# rc4_1_1.net
KiCad netlist of a schematic drawn in EAGLE
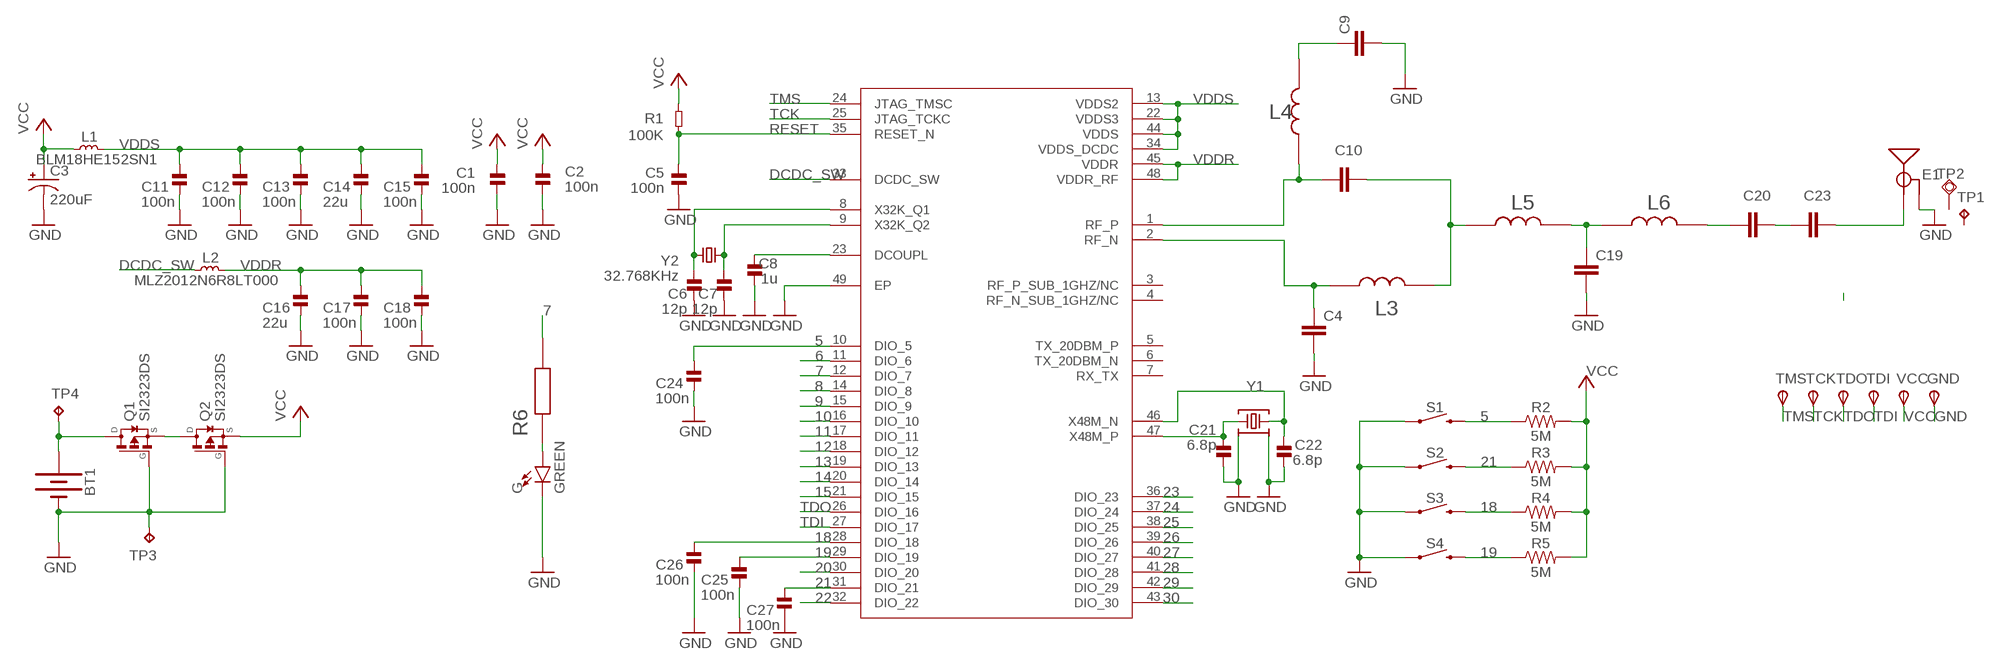
[diagram p0: schematic, sheet 1]

(export (version "E")
  (design (tool "Eeschema 10.0.6"))
  (components
    (comp (ref "BT1")
      (value "BATTERY-20MM_SMD_4LEGS_OVERPASTE")
      (footprint "eagle-import:BATTCON_20MM_4LEGS_OVERPASTE")
      (libsource (lib "eagle-import") (part "BATTERY-20MM_SMD_4LEGS_OVERPASTE"))
    )
    (comp (ref "C1")
      (value "100n")
      (footprint "eagle-import:_PKG_C_0402")
      (libsource (lib "eagle-import") (part "CAP-0402"))
    )
    (comp (ref "C2")
      (value "100n")
      (footprint "eagle-import:_PKG_C_0402")
      (libsource (lib "eagle-import") (part "CAP-0402"))
    )
    (comp (ref "C3")
      (value "220uF")
      (footprint "eagle-import:EIA3528")
      (libsource (lib "eagle-import") (part "47UF-POLAR-EIA3528-10V-10%"))
    )
    (comp (ref "C4")
      (value "1pf")
      (footprint "eagle-import:CAPC1005X40N")
      (fields (field (name "MF") "Yageo") (field (name "MP") "RC0402FR-073M6L"))
      (libsource (lib "eagle-import") (part "CAP0402"))
    )
    (comp (ref "C5")
      (value "100n")
      (footprint "eagle-import:_PKG_C_0402")
      (libsource (lib "eagle-import") (part "CAP-0402"))
    )
    (comp (ref "C6")
      (value "12p")
      (footprint "eagle-import:_PKG_C_0402")
      (libsource (lib "eagle-import") (part "CAP-0402"))
    )
    (comp (ref "C7")
      (value "12p")
      (footprint "eagle-import:_PKG_C_0402")
      (libsource (lib "eagle-import") (part "CAP-0402"))
    )
    (comp (ref "C8")
      (value "1u")
      (footprint "eagle-import:_PKG_C_0402")
      (libsource (lib "eagle-import") (part "CAP-0402"))
    )
    (comp (ref "C9")
      (value "12pF")
      (footprint "eagle-import:CAPC1005X40N")
      (fields (field (name "MF") "Yageo") (field (name "MP") "RC0402FR-073M6L"))
      (libsource (lib "eagle-import") (part "CAP0402"))
    )
    (comp (ref "C10")
      (value "1pF")
      (footprint "eagle-import:CAPC1005X40N")
      (fields (field (name "MF") "Yageo") (field (name "MP") "RC0402FR-073M6L"))
      (libsource (lib "eagle-import") (part "CAP0402"))
    )
    (comp (ref "C11")
      (value "100n")
      (footprint "eagle-import:_PKG_C_0402")
      (libsource (lib "eagle-import") (part "CAP-0402"))
    )
    (comp (ref "C12")
      (value "100n")
      (footprint "eagle-import:_PKG_C_0402")
      (libsource (lib "eagle-import") (part "CAP-0402"))
    )
    (comp (ref "C13")
      (value "100n")
      (footprint "eagle-import:_PKG_C_0402")
      (libsource (lib "eagle-import") (part "CAP-0402"))
    )
    (comp (ref "C14")
      (value "22u")
      (footprint "eagle-import:_PKG_C_0805")
      (libsource (lib "eagle-import") (part "CAP-0805"))
    )
    (comp (ref "C15")
      (value "100n")
      (footprint "eagle-import:_PKG_C_0402")
      (libsource (lib "eagle-import") (part "CAP-0402"))
    )
    (comp (ref "C16")
      (value "22u")
      (footprint "eagle-import:_PKG_C_0805")
      (libsource (lib "eagle-import") (part "CAP-0805"))
    )
    (comp (ref "C17")
      (value "100n")
      (footprint "eagle-import:_PKG_C_0402")
      (libsource (lib "eagle-import") (part "CAP-0402"))
    )
    (comp (ref "C18")
      (value "100n")
      (footprint "eagle-import:_PKG_C_0402")
      (libsource (lib "eagle-import") (part "CAP-0402"))
    )
    (comp (ref "C19")
      (value "1pF")
      (footprint "eagle-import:CAPC1005X40N")
      (fields (field (name "MF") "Yageo") (field (name "MP") "RC0402FR-073M6L"))
      (libsource (lib "eagle-import") (part "CAP0402"))
    )
    (comp (ref "C20")
      (value "12p")
      (footprint "eagle-import:CAPC1005X40N")
      (fields (field (name "MF") "Yageo") (field (name "MP") "RC0402FR-073M6L"))
      (libsource (lib "eagle-import") (part "CAP0402"))
    )
    (comp (ref "C21")
      (value "6.8p")
      (footprint "eagle-import:_PKG_C_0402")
      (libsource (lib "eagle-import") (part "CAP-0402"))
    )
    (comp (ref "C22")
      (value "6.8p")
      (footprint "eagle-import:_PKG_C_0402")
      (libsource (lib "eagle-import") (part "CAP-0402"))
    )
    (comp (ref "C23")
      (value "1.8pF")
      (footprint "eagle-import:CAPC1005X40N")
      (fields (field (name "MF") "Yageo") (field (name "MP") "RC0402FR-073M6L"))
      (libsource (lib "eagle-import") (part "CAP0402"))
    )
    (comp (ref "C24")
      (value "100n")
      (footprint "eagle-import:_PKG_C_0402")
      (libsource (lib "eagle-import") (part "CAP-0402"))
    )
    (comp (ref "C25")
      (value "100n")
      (footprint "eagle-import:_PKG_C_0402")
      (libsource (lib "eagle-import") (part "CAP-0402"))
    )
    (comp (ref "C26")
      (value "100n")
      (footprint "eagle-import:_PKG_C_0402")
      (libsource (lib "eagle-import") (part "CAP-0402"))
    )
    (comp (ref "C27")
      (value "100n")
      (footprint "eagle-import:_PKG_C_0402")
      (libsource (lib "eagle-import") (part "CAP-0402"))
    )
    (comp (ref "E1")
      (value "ANTENNA-GROUNDEDTRACE-15.2MM")
      (footprint "eagle-import:TRACE_ANTENNA_2.4GHZ_15.2MM")
      (libsource (lib "eagle-import") (part "ANTENNA-GROUNDEDTRACE-15.2MM"))
    )
    (comp (ref "G")
      (value "GREEN")
      (footprint "eagle-import:LED-0603")
      (libsource (lib "eagle-import") (part "LED-GREEN0603"))
    )
    (comp (ref "GND")
      (value "TPSTP11R")
      (footprint "eagle-import:TP11R")
      (libsource (lib "eagle-import") (part "TPSTP11R"))
    )
    (comp (ref "IC3")
      (value "CC2652R1FRGZ")
      (footprint "eagle-import:RGZ0048A-IPC_B")
      (fields
        (field (name "MANUFACTURER_PART_NUMBER") "CC2652P1FRGZR")
        (field (name "COPYRIGHT") "Copyright (C) 2022 Ultra Librarian. All rights reserved.")
      )
      (libsource (lib "eagle-import") (part "CC2652P1FRGZRRGZ0048A-IPC_B"))
    )
    (comp (ref "L1")
      (value "BLM18HE152SN1")
      (footprint "eagle-import:_PKG_L_0603")
      (libsource (lib "eagle-import") (part "INDUCTOR-0603"))
    )
    (comp (ref "L2")
      (value "MLZ2012N6R8LT000")
      (footprint "eagle-import:_PKG_C_0805")
      (libsource (lib "eagle-import") (part "INDUCTOR-0805"))
    )
    (comp (ref "L3")
      (value "2.4nH")
      (footprint "eagle-import:INDC1005X40N")
      (fields (field (name "MF") "Yageo") (field (name "MP") "RC0402FR-073M6L"))
      (libsource (lib "eagle-import") (part "IND0402IND0402"))
    )
    (comp (ref "L4")
      (value "2.4nH")
      (footprint "eagle-import:INDC1005X40N")
      (fields (field (name "MF") "Yageo") (field (name "MP") "RC0402FR-073M6L"))
      (libsource (lib "eagle-import") (part "IND0402IND0402"))
    )
    (comp (ref "L5")
      (value "2nH")
      (footprint "eagle-import:INDC1005X40N")
      (fields (field (name "MF") "Yageo") (field (name "MP") "RC0402FR-073M6L"))
      (libsource (lib "eagle-import") (part "IND0402IND0402"))
    )
    (comp (ref "L6")
      (value "2nH")
      (footprint "eagle-import:INDC1005X40N")
      (fields (field (name "MF") "Yageo") (field (name "MP") "RC0402FR-073M6L"))
      (libsource (lib "eagle-import") (part "IND0402IND0402"))
    )
    (comp (ref "Q1")
      (value "SI2323DS")
      (footprint "eagle-import:SOT23")
      (fields (field (name "MF") "Vishay Siliconix"))
      (libsource (lib "eagle-import") (part "SI2323DS"))
    )
    (comp (ref "Q2")
      (value "SI2323DS")
      (footprint "eagle-import:SOT23")
      (fields (field (name "MF") "Vishay Siliconix"))
      (libsource (lib "eagle-import") (part "SI2323DS"))
    )
    (comp (ref "R1")
      (value "100K")
      (footprint "eagle-import:_PKG_C_0402")
      (libsource (lib "eagle-import") (part "RES-0402"))
    )
    (comp (ref "R2")
      (value "5M")
      (footprint "eagle-import:0603")
      (libsource (lib "eagle-import") (part "2.49KOHM-0603-1/10W-1%"))
    )
    (comp (ref "R3")
      (value "5M")
      (footprint "eagle-import:0603")
      (libsource (lib "eagle-import") (part "2.49KOHM-0603-1/10W-1%"))
    )
    (comp (ref "R4")
      (value "5M")
      (footprint "eagle-import:0603")
      (libsource (lib "eagle-import") (part "2.49KOHM-0603-1/10W-1%"))
    )
    (comp (ref "R5")
      (value "5M")
      (footprint "eagle-import:0603")
      (libsource (lib "eagle-import") (part "2.49KOHM-0603-1/10W-1%"))
    )
    (comp (ref "R6")
      (value "2.2k")
      (footprint "eagle-import:RESC1005X40N")
      (fields (field (name "MF") "Yageo") (field (name "MP") "RC0402FR-073M6L"))
      (libsource (lib "eagle-import") (part "RES0402"))
    )
    (comp (ref "S1")
      (value "MOMENTARY-SWITCH-SPST-SMD-5.2MM")
      (footprint "eagle-import:TACTILE_SWITCH_SMD_5.2MM")
      (libsource (lib "eagle-import") (part "MOMENTARY-SWITCH-SPST-SMD-5.2MM"))
    )
    (comp (ref "S2")
      (value "MOMENTARY-SWITCH-SPST-SMD-5.2MM")
      (footprint "eagle-import:TACTILE_SWITCH_SMD_5.2MM")
      (libsource (lib "eagle-import") (part "MOMENTARY-SWITCH-SPST-SMD-5.2MM"))
    )
    (comp (ref "S3")
      (value "MOMENTARY-SWITCH-SPST-SMD-5.2MM")
      (footprint "eagle-import:TACTILE_SWITCH_SMD_5.2MM")
      (libsource (lib "eagle-import") (part "MOMENTARY-SWITCH-SPST-SMD-5.2MM"))
    )
    (comp (ref "S4")
      (value "MOMENTARY-SWITCH-SPST-SMD-5.2MM")
      (footprint "eagle-import:TACTILE_SWITCH_SMD_5.2MM")
      (libsource (lib "eagle-import") (part "MOMENTARY-SWITCH-SPST-SMD-5.2MM"))
    )
    (comp (ref "TCK")
      (value "TPSTP11R")
      (footprint "eagle-import:TP11R")
      (libsource (lib "eagle-import") (part "TPSTP11R"))
    )
    (comp (ref "TDI")
      (value "TPSTP11R")
      (footprint "eagle-import:TP11R")
      (libsource (lib "eagle-import") (part "TPSTP11R"))
    )
    (comp (ref "TDO")
      (value "TPSTP11R")
      (footprint "eagle-import:TP11R")
      (libsource (lib "eagle-import") (part "TPSTP11R"))
    )
    (comp (ref "TMS")
      (value "TPSTP11R")
      (footprint "eagle-import:TP11R")
      (libsource (lib "eagle-import") (part "TPSTP11R"))
    )
    (comp (ref "TP1")
      (value "TPTP06SQ")
      (footprint "eagle-import:TP05SQ")
      (libsource (lib "eagle-import") (part "TPTP06SQ"))
    )
    (comp (ref "TP2")
      (value "TPSQTP15SQ")
      (footprint "eagle-import:TP15SQ")
      (libsource (lib "eagle-import") (part "TPSQTP15SQ"))
    )
    (comp (ref "TP3")
      (value "TPB2,54")
      (footprint "eagle-import:B2,54")
      (libsource (lib "eagle-import") (part "testpad_385_TPB2,54"))
    )
    (comp (ref "TP4")
      (value "TPB2,54")
      (footprint "eagle-import:B2,54")
      (libsource (lib "eagle-import") (part "testpad_385_TPB2,54"))
    )
    (comp (ref "VCC")
      (value "TPSTP11R")
      (footprint "eagle-import:TP11R")
      (libsource (lib "eagle-import") (part "TPSTP11R"))
    )
    (comp (ref "Y1")
      (value "Q22FA12800150")
      (footprint "eagle-import:XTAL-4P-2016")
      (fields (field (name "DIGIKEY_PART") "1253-2042-1-ND") (field (name "MFG_PART") "CX2016DB48000C0FPLC1"))
      (libsource (lib "eagle-import") (part "48.000MHZ_CX2016DB48000C0FPLC1"))
    )
    (comp (ref "Y2")
      (value "32.768KHz")
      (footprint "eagle-import:XTAL-2P-3215")
      (fields (field (name "LCSC_PART") "C32346") (field (name "MFG_PART") "Q13FC1350000400"))
      (libsource (lib "eagle-import") (part "32.768KHZ_Q13FC1350000400"))
    )
  )
  (nets
    (net (code "1") (name "/5") (class "Default")
      (node (ref "C24") (pin "1") (pinfunction "1_1") (pintype "passive"))
      (node (ref "IC3") (pin "10") (pinfunction "DIO_5_10") (pintype "bidirectional"))
      (node (ref "R2") (pin "1") (pinfunction "1_1") (pintype "passive"))
      (node (ref "S1") (pin "3") (pinfunction "2_3") (pintype "passive"))
    )
    (net (code "2") (name "/6") (class "Default")
      (node (ref "IC3") (pin "11") (pinfunction "DIO_6_11") (pintype "bidirectional"))
    )
    (net (code "3") (name "/7") (class "Default")
      (node (ref "IC3") (pin "12") (pinfunction "DIO_7_12") (pintype "bidirectional"))
      (node (ref "R6") (pin "2") (pinfunction "2_2") (pintype "passive"))
    )
    (net (code "4") (name "/8") (class "Default")
      (node (ref "IC3") (pin "14") (pinfunction "DIO_8_14") (pintype "bidirectional"))
    )
    (net (code "5") (name "/9") (class "Default")
      (node (ref "IC3") (pin "15") (pinfunction "DIO_9_15") (pintype "bidirectional"))
    )
    (net (code "6") (name "/10") (class "Default")
      (node (ref "IC3") (pin "16") (pinfunction "DIO_10_16") (pintype "bidirectional"))
    )
    (net (code "7") (name "/11") (class "Default")
      (node (ref "IC3") (pin "17") (pinfunction "DIO_11_17") (pintype "bidirectional"))
    )
    (net (code "8") (name "/12") (class "Default")
      (node (ref "IC3") (pin "18") (pinfunction "DIO_12_18") (pintype "bidirectional"))
    )
    (net (code "9") (name "/13") (class "Default")
      (node (ref "IC3") (pin "19") (pinfunction "DIO_13_19") (pintype "bidirectional"))
    )
    (net (code "10") (name "/14") (class "Default")
      (node (ref "IC3") (pin "20") (pinfunction "DIO_14_20") (pintype "bidirectional"))
    )
    (net (code "11") (name "/15") (class "Default")
      (node (ref "IC3") (pin "21") (pinfunction "DIO_15_21") (pintype "bidirectional"))
    )
    (net (code "12") (name "/18") (class "Default")
      (node (ref "C26") (pin "1") (pinfunction "1_1") (pintype "passive"))
      (node (ref "IC3") (pin "28") (pinfunction "DIO_18_28") (pintype "bidirectional"))
      (node (ref "R4") (pin "1") (pinfunction "1_1") (pintype "passive"))
      (node (ref "S3") (pin "3") (pinfunction "2_3") (pintype "passive"))
    )
    (net (code "13") (name "/19") (class "Default")
      (node (ref "C25") (pin "1") (pinfunction "1_1") (pintype "passive"))
      (node (ref "IC3") (pin "29") (pinfunction "DIO_19_29") (pintype "bidirectional"))
      (node (ref "R5") (pin "1") (pinfunction "1_1") (pintype "passive"))
      (node (ref "S4") (pin "3") (pinfunction "2_3") (pintype "passive"))
    )
    (net (code "14") (name "/20") (class "Default")
      (node (ref "IC3") (pin "30") (pinfunction "DIO_20_30") (pintype "bidirectional"))
    )
    (net (code "15") (name "/21") (class "Default")
      (node (ref "C27") (pin "1") (pinfunction "1_1") (pintype "passive"))
      (node (ref "IC3") (pin "31") (pinfunction "DIO_21_31") (pintype "bidirectional"))
      (node (ref "R3") (pin "1") (pinfunction "1_1") (pintype "passive"))
      (node (ref "S2") (pin "3") (pinfunction "2_3") (pintype "passive"))
    )
    (net (code "16") (name "/22") (class "Default")
      (node (ref "IC3") (pin "32") (pinfunction "DIO_22_32") (pintype "bidirectional"))
    )
    (net (code "17") (name "/23") (class "Default")
      (node (ref "IC3") (pin "36") (pinfunction "DIO_23_36") (pintype "bidirectional"))
    )
    (net (code "18") (name "/24") (class "Default")
      (node (ref "IC3") (pin "37") (pinfunction "DIO_24_37") (pintype "bidirectional"))
    )
    (net (code "19") (name "/25") (class "Default")
      (node (ref "IC3") (pin "38") (pinfunction "DIO_25_38") (pintype "bidirectional"))
    )
    (net (code "20") (name "/26") (class "Default")
      (node (ref "IC3") (pin "39") (pinfunction "DIO_26_39") (pintype "bidirectional"))
    )
    (net (code "21") (name "/27") (class "Default")
      (node (ref "IC3") (pin "40") (pinfunction "DIO_27_40") (pintype "bidirectional"))
    )
    (net (code "22") (name "/28") (class "Default")
      (node (ref "IC3") (pin "41") (pinfunction "DIO_28_41") (pintype "bidirectional"))
    )
    (net (code "23") (name "/29") (class "Default")
      (node (ref "IC3") (pin "42") (pinfunction "DIO_29_42") (pintype "bidirectional"))
    )
    (net (code "24") (name "/30") (class "Default")
      (node (ref "IC3") (pin "43") (pinfunction "DIO_30_43") (pintype "bidirectional"))
    )
    (net (code "25") (name "/DCDC_SW") (class "Default")
      (node (ref "IC3") (pin "33") (pinfunction "DCDC_SW_33") (pintype "power_in"))
      (node (ref "L2") (pin "1") (pinfunction "1_1") (pintype "passive"))
    )
    (net (code "26") (name "/RESET") (class "Default")
      (node (ref "C5") (pin "2") (pinfunction "2_2") (pintype "passive"))
      (node (ref "IC3") (pin "35") (pinfunction "RESET_N_35") (pintype "input"))
      (node (ref "R1") (pin "1") (pinfunction "1_1") (pintype "passive"))
    )
    (net (code "27") (name "/TCK") (class "Default")
      (node (ref "IC3") (pin "25") (pinfunction "JTAG_TCKC_25") (pintype "input"))
      (node (ref "TCK") (pin "TP") (pinfunction "PP_TP") (pintype "input"))
    )
    (net (code "28") (name "/TDI") (class "Default")
      (node (ref "IC3") (pin "27") (pinfunction "DIO_17_27") (pintype "bidirectional"))
      (node (ref "TDI") (pin "TP") (pinfunction "PP_TP") (pintype "input"))
    )
    (net (code "29") (name "/TDO") (class "Default")
      (node (ref "IC3") (pin "26") (pinfunction "DIO_16_26") (pintype "bidirectional"))
      (node (ref "TDO") (pin "TP") (pinfunction "PP_TP") (pintype "input"))
    )
    (net (code "30") (name "/TMS") (class "Default")
      (node (ref "IC3") (pin "24") (pinfunction "JTAG_TMSC_24") (pintype "bidirectional"))
      (node (ref "TMS") (pin "TP") (pinfunction "PP_TP") (pintype "input"))
    )
    (net (code "31") (name "/VDDR") (class "Default")
      (node (ref "C16") (pin "1") (pinfunction "1_1") (pintype "passive"))
      (node (ref "C17") (pin "1") (pinfunction "1_1") (pintype "passive"))
      (node (ref "C18") (pin "1") (pinfunction "1_1") (pintype "passive"))
      (node (ref "IC3") (pin "45") (pinfunction "VDDR_45") (pintype "power_in"))
      (node (ref "IC3") (pin "48") (pinfunction "VDDR_RF_48") (pintype "power_in"))
      (node (ref "L2") (pin "2") (pinfunction "2_2") (pintype "passive"))
    )
    (net (code "32") (name "/VDDS") (class "Default")
      (node (ref "C11") (pin "1") (pinfunction "1_1") (pintype "passive"))
      (node (ref "C12") (pin "1") (pinfunction "1_1") (pintype "passive"))
      (node (ref "C13") (pin "1") (pinfunction "1_1") (pintype "passive"))
      (node (ref "C14") (pin "1") (pinfunction "1_1") (pintype "passive"))
      (node (ref "C15") (pin "1") (pinfunction "1_1") (pintype "passive"))
      (node (ref "IC3") (pin "13") (pinfunction "VDDS2_13") (pintype "power_in"))
      (node (ref "IC3") (pin "22") (pinfunction "VDDS3_22") (pintype "bidirectional"))
      (node (ref "IC3") (pin "34") (pinfunction "VDDS_DCDC_34") (pintype "power_in"))
      (node (ref "IC3") (pin "44") (pinfunction "VDDS_44") (pintype "power_in"))
      (node (ref "L1") (pin "2") (pinfunction "2_2") (pintype "passive"))
    )
    (net (code "33") (name "GND") (class "Default")
      (node (ref "BT1") (pin "2") (pinfunction "-_2") (pintype "power_in"))
      (node (ref "C1") (pin "1") (pinfunction "1_1") (pintype "passive"))
      (node (ref "C11") (pin "2") (pinfunction "2_2") (pintype "passive"))
      (node (ref "C12") (pin "2") (pinfunction "2_2") (pintype "passive"))
      (node (ref "C13") (pin "2") (pinfunction "2_2") (pintype "passive"))
      (node (ref "C14") (pin "2") (pinfunction "2_2") (pintype "passive"))
      (node (ref "C15") (pin "2") (pinfunction "2_2") (pintype "passive"))
      (node (ref "C16") (pin "2") (pinfunction "2_2") (pintype "passive"))
      (node (ref "C17") (pin "2") (pinfunction "2_2") (pintype "passive"))
      (node (ref "C18") (pin "2") (pinfunction "2_2") (pintype "passive"))
      (node (ref "C19") (pin "2") (pinfunction "2_2") (pintype "passive"))
      (node (ref "C2") (pin "1") (pinfunction "1_1") (pintype "passive"))
      (node (ref "C21") (pin "1") (pinfunction "1_1") (pintype "passive"))
      (node (ref "C22") (pin "1") (pinfunction "1_1") (pintype "passive"))
      (node (ref "C24") (pin "2") (pinfunction "2_2") (pintype "passive"))
      (node (ref "C25") (pin "2") (pinfunction "2_2") (pintype "passive"))
      (node (ref "C26") (pin "2") (pinfunction "2_2") (pintype "passive"))
      (node (ref "C27") (pin "2") (pinfunction "2_2") (pintype "passive"))
      (node (ref "C3") (pin "C") (pinfunction "-_C") (pintype "passive"))
      (node (ref "C4") (pin "2") (pinfunction "2_2") (pintype "passive"))
      (node (ref "C5") (pin "1") (pinfunction "1_1") (pintype "passive"))
      (node (ref "C6") (pin "1") (pinfunction "1_1") (pintype "passive"))
      (node (ref "C7") (pin "1") (pinfunction "1_1") (pintype "passive"))
      (node (ref "C8") (pin "1") (pinfunction "1_1") (pintype "passive"))
      (node (ref "C9") (pin "2") (pinfunction "2_2") (pintype "passive"))
      (node (ref "E1") (pin "GND") (pinfunction "GND_GND") (pintype "bidirectional"))
      (node (ref "G") (pin "C") (pinfunction "C_C") (pintype "passive"))
      (node (ref "GND") (pin "TP") (pinfunction "PP_TP") (pintype "input"))
      (node (ref "IC3") (pin "49") (pinfunction "EP_49") (pintype "power_in"))
      (node (ref "Q1") (pin "1") (pinfunction "G_1") (pintype "passive"))
      (node (ref "Q2") (pin "1") (pinfunction "G_1") (pintype "passive"))
      (node (ref "S1") (pin "1") (pinfunction "1_1") (pintype "passive"))
      (node (ref "S2") (pin "1") (pinfunction "1_1") (pintype "passive"))
      (node (ref "S3") (pin "1") (pinfunction "1_1") (pintype "passive"))
      (node (ref "S4") (pin "1") (pinfunction "1_1") (pintype "passive"))
      (node (ref "TP3") (pin "TP") (pinfunction "TP_TP") (pintype "input"))
      (node (ref "Y1") (pin "2") (pinfunction "2_2") (pintype "bidirectional"))
      (node (ref "Y1") (pin "4") (pinfunction "4_4") (pintype "bidirectional"))
    )
    (net (code "34") (name "Net-(BT1-+)") (class "Default")
      (node (ref "BT1") (pin "1") (pinfunction "+_1") (pintype "power_in"))
      (node (ref "Q1") (pin "3") (pinfunction "D_3") (pintype "passive"))
      (node (ref "TP4") (pin "TP") (pinfunction "TP_TP") (pintype "input"))
    )
    (net (code "35") (name "Net-(C9-Pad1)") (class "Default")
      (node (ref "C9") (pin "1") (pinfunction "1_1") (pintype "passive"))
      (node (ref "L4") (pin "2") (pinfunction "2_2") (pintype "passive"))
    )
    (net (code "36") (name "Net-(C10-Pad2)") (class "Default")
      (node (ref "C10") (pin "2") (pinfunction "2_2") (pintype "passive"))
      (node (ref "L3") (pin "2") (pinfunction "2_2") (pintype "passive"))
      (node (ref "L5") (pin "1") (pinfunction "1_1") (pintype "passive"))
    )
    (net (code "37") (name "Net-(C19-Pad1)") (class "Default")
      (node (ref "C19") (pin "1") (pinfunction "1_1") (pintype "passive"))
      (node (ref "L5") (pin "2") (pinfunction "2_2") (pintype "passive"))
      (node (ref "L6") (pin "1") (pinfunction "1_1") (pintype "passive"))
    )
    (net (code "38") (name "Net-(C20-Pad1)") (class "Default")
      (node (ref "C20") (pin "1") (pinfunction "1_1") (pintype "passive"))
      (node (ref "L6") (pin "2") (pinfunction "2_2") (pintype "passive"))
    )
    (net (code "39") (name "Net-(C20-Pad2)") (class "Default")
      (node (ref "C20") (pin "2") (pinfunction "2_2") (pintype "passive"))
      (node (ref "C23") (pin "1") (pinfunction "1_1") (pintype "passive"))
    )
    (net (code "40") (name "Net-(E1-SIGNAL)") (class "Default")
      (node (ref "C23") (pin "2") (pinfunction "2_2") (pintype "passive"))
      (node (ref "E1") (pin "ANT") (pinfunction "SIGNAL_ANT") (pintype "bidirectional"))
    )
    (net (code "41") (name "Net-(G-PadA)") (class "Default")
      (node (ref "G") (pin "A") (pinfunction "A_A") (pintype "passive"))
      (node (ref "R6") (pin "1") (pinfunction "1_1") (pintype "passive"))
    )
    (net (code "42") (name "Net-(IC3-DCOUPL)") (class "Default")
      (node (ref "C8") (pin "2") (pinfunction "2_2") (pintype "passive"))
      (node (ref "IC3") (pin "23") (pinfunction "DCOUPL_23") (pintype "power_in"))
    )
    (net (code "43") (name "Net-(IC3-RF_N)") (class "Default")
      (node (ref "C4") (pin "1") (pinfunction "1_1") (pintype "passive"))
      (node (ref "IC3") (pin "2") (pinfunction "RF_N_2") (pintype "passive"))
      (node (ref "L3") (pin "1") (pinfunction "1_1") (pintype "passive"))
    )
    (net (code "44") (name "Net-(IC3-RF_P)") (class "Default")
      (node (ref "C10") (pin "1") (pinfunction "1_1") (pintype "passive"))
      (node (ref "IC3") (pin "1") (pinfunction "RF_P_1") (pintype "passive"))
      (node (ref "L4") (pin "1") (pinfunction "1_1") (pintype "passive"))
    )
    (net (code "45") (name "Net-(IC3-X32K_Q1)") (class "Default")
      (node (ref "C6") (pin "2") (pinfunction "2_2") (pintype "passive"))
      (node (ref "IC3") (pin "8") (pinfunction "X32K_Q1_8") (pintype "passive"))
      (node (ref "Y2") (pin "1") (pinfunction "1_1") (pintype "passive"))
    )
    (net (code "46") (name "Net-(IC3-X32K_Q2)") (class "Default")
      (node (ref "C7") (pin "2") (pinfunction "2_2") (pintype "passive"))
      (node (ref "IC3") (pin "9") (pinfunction "X32K_Q2_9") (pintype "passive"))
      (node (ref "Y2") (pin "2") (pinfunction "2_2") (pintype "passive"))
    )
    (net (code "47") (name "Net-(IC3-X48M_N)") (class "Default")
      (node (ref "C22") (pin "2") (pinfunction "2_2") (pintype "passive"))
      (node (ref "IC3") (pin "46") (pinfunction "X48M_N_46") (pintype "passive"))
      (node (ref "Y1") (pin "3") (pinfunction "3_3") (pintype "passive"))
    )
    (net (code "48") (name "Net-(IC3-X48M_P)") (class "Default")
      (node (ref "C21") (pin "2") (pinfunction "2_2") (pintype "passive"))
      (node (ref "IC3") (pin "47") (pinfunction "X48M_P_47") (pintype "passive"))
      (node (ref "Y1") (pin "1") (pinfunction "1_1") (pintype "passive"))
    )
    (net (code "49") (name "Net-(Q1-S)") (class "Default")
      (node (ref "Q1") (pin "2") (pinfunction "S_2") (pintype "passive"))
      (node (ref "Q2") (pin "3") (pinfunction "D_3") (pintype "passive"))
    )
    (net (code "50") (name "VCC") (class "Default")
      (node (ref "C1") (pin "2") (pinfunction "2_2") (pintype "passive"))
      (node (ref "C2") (pin "2") (pinfunction "2_2") (pintype "passive"))
      (node (ref "C3") (pin "A") (pinfunction "+_A") (pintype "passive"))
      (node (ref "L1") (pin "1") (pinfunction "1_1") (pintype "passive"))
      (node (ref "Q2") (pin "2") (pinfunction "S_2") (pintype "passive"))
      (node (ref "R1") (pin "2") (pinfunction "2_2") (pintype "passive"))
      (node (ref "R2") (pin "2") (pinfunction "2_2") (pintype "passive"))
      (node (ref "R3") (pin "2") (pinfunction "2_2") (pintype "passive"))
      (node (ref "R4") (pin "2") (pinfunction "2_2") (pintype "passive"))
      (node (ref "R5") (pin "2") (pinfunction "2_2") (pintype "passive"))
      (node (ref "VCC") (pin "TP") (pinfunction "PP_TP") (pintype "input"))
    )
    (net (code "51") (name "unconnected-(IC3-RF_N_SUB_1GHZ{slash}NC-Pad4)") (class "Default")
      (node (ref "IC3") (pin "4") (pinfunction "RF_N_SUB_1GHZ/NC_4") (pintype "passive"))
    )
    (net (code "52") (name "unconnected-(IC3-RF_P_SUB_1GHZ{slash}NC-Pad3)") (class "Default")
      (node (ref "IC3") (pin "3") (pinfunction "RF_P_SUB_1GHZ/NC_3") (pintype "passive"))
    )
    (net (code "53") (name "unconnected-(IC3-RX_TX-Pad7)") (class "Default")
      (node (ref "IC3") (pin "7") (pinfunction "RX_TX_7") (pintype "passive"))
    )
    (net (code "54") (name "unconnected-(IC3-TX_20DBM_N-Pad6)") (class "Default")
      (node (ref "IC3") (pin "6") (pinfunction "TX_20DBM_N_6") (pintype "passive"))
    )
    (net (code "55") (name "unconnected-(IC3-TX_20DBM_P-Pad5)") (class "Default")
      (node (ref "IC3") (pin "5") (pinfunction "TX_20DBM_P_5") (pintype "passive"))
    )
    (net (code "56") (name "unconnected-(TP1-PadTP)") (class "Default")
      (node (ref "TP1") (pin "TP") (pinfunction "TP_TP") (pintype "input"))
    )
    (net (code "57") (name "unconnected-(TP2-PadTP)") (class "Default")
      (node (ref "TP2") (pin "TP") (pinfunction "TP_TP") (pintype "input"))
    )
  )
)
